# MCU.net
KiCad netlist of a schematic drawn in EAGLE
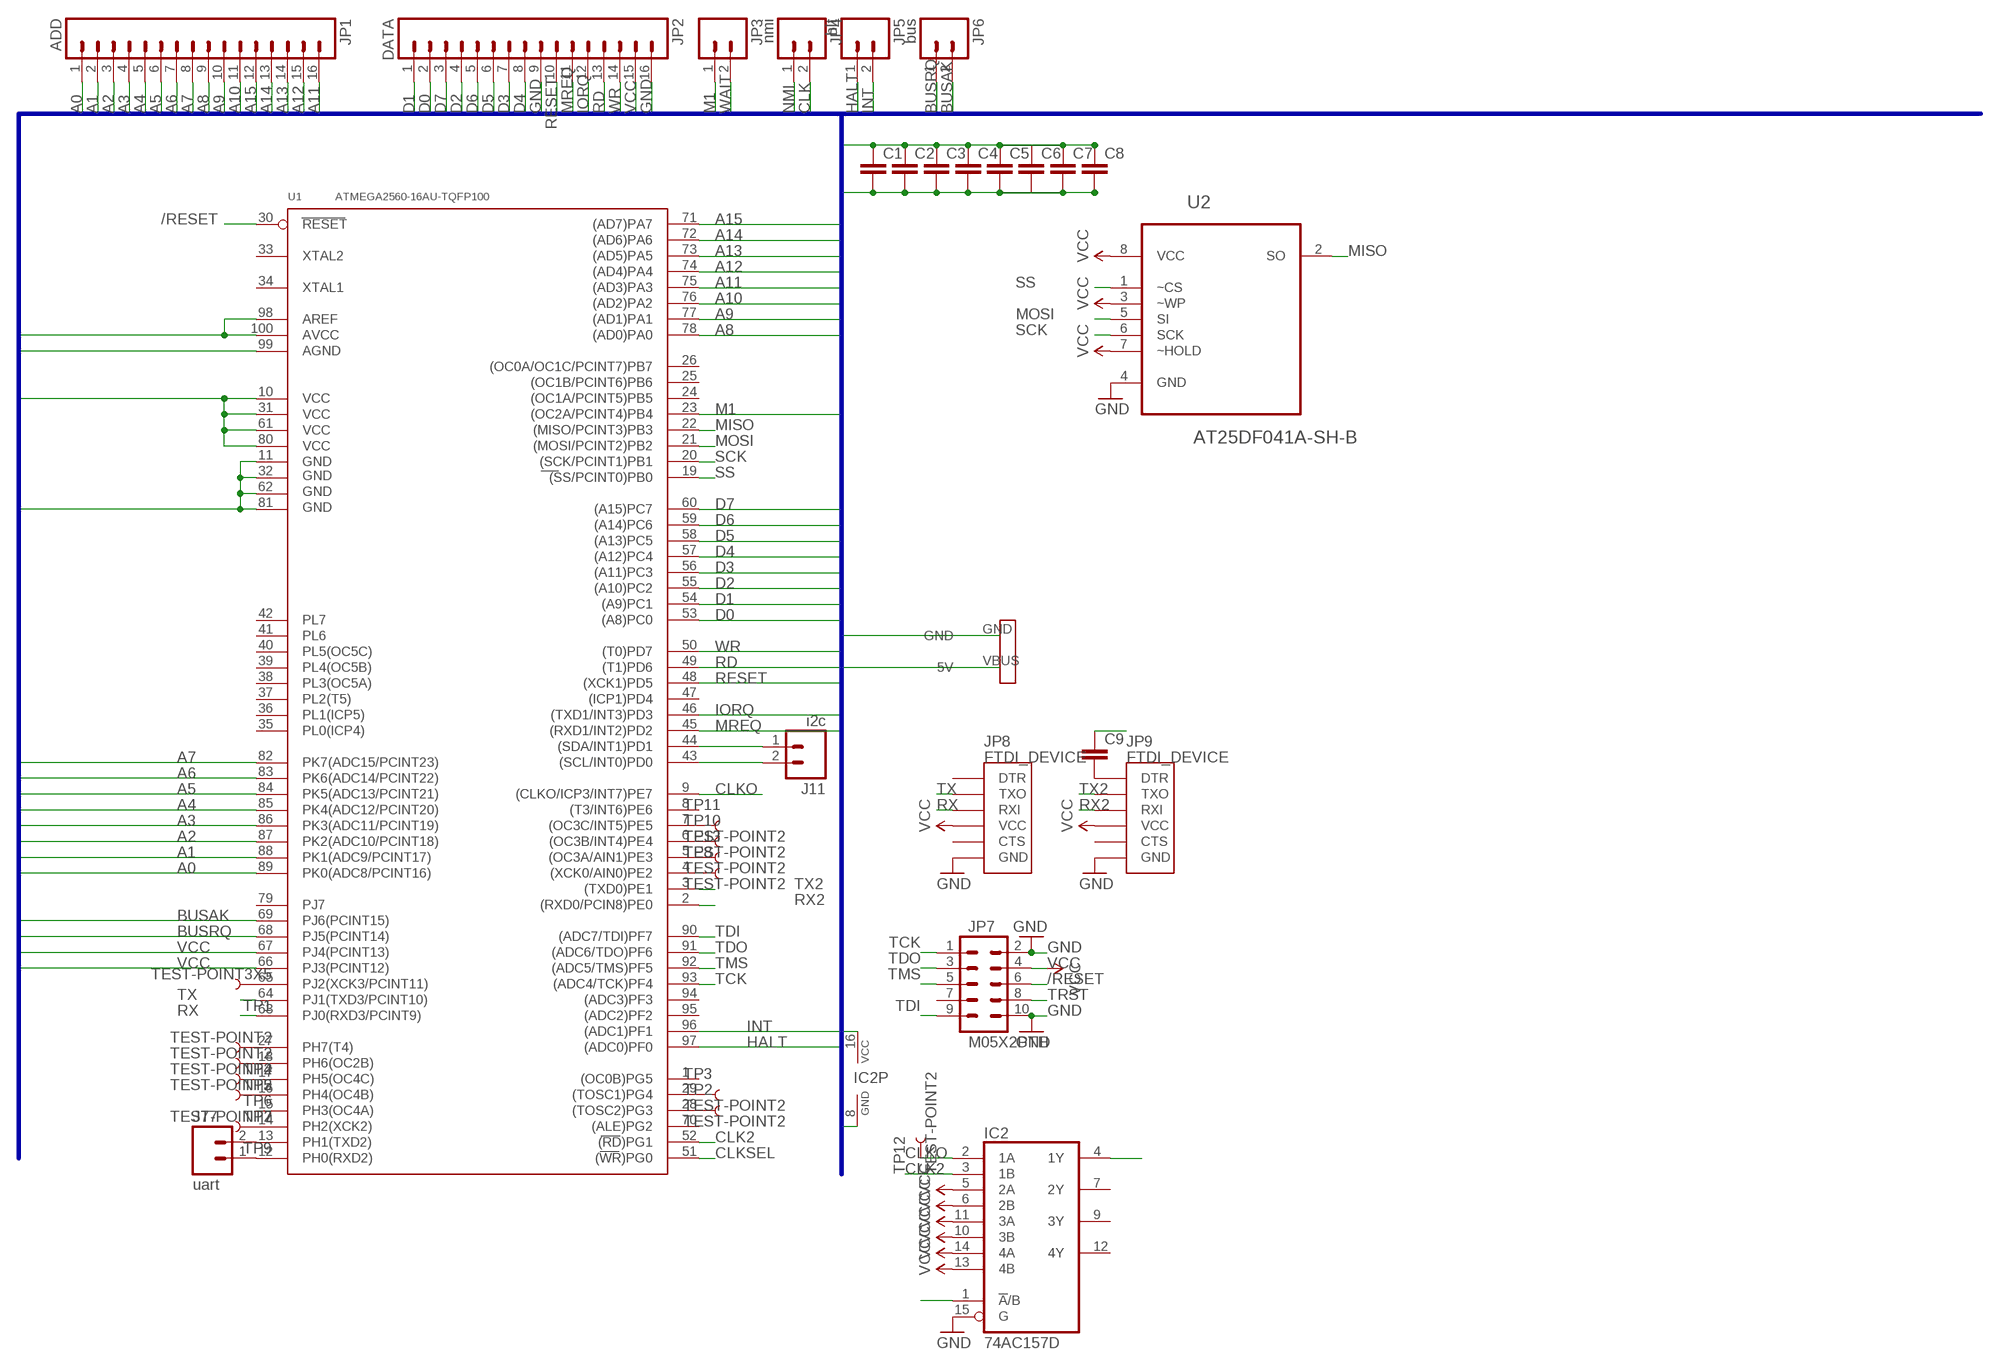
[diagram p0: schematic, sheet 1]

(export (version "E")
  (design (tool "Eeschema 10.0.6"))
  (components
    (comp (ref "C1")
      (value "C-EUC0805")
      (footprint "eagle-import:C0805")
      (libsource (lib "eagle-import") (part "C-EUC0805"))
    )
    (comp (ref "C2")
      (value "C-EUC0805")
      (footprint "eagle-import:C0805")
      (libsource (lib "eagle-import") (part "C-EUC0805"))
    )
    (comp (ref "C3")
      (value "C-EUC0805")
      (footprint "eagle-import:C0805")
      (libsource (lib "eagle-import") (part "C-EUC0805"))
    )
    (comp (ref "C4")
      (value "C-EUC0805")
      (footprint "eagle-import:C0805")
      (libsource (lib "eagle-import") (part "C-EUC0805"))
    )
    (comp (ref "C5")
      (value "C-EUC0805")
      (footprint "eagle-import:C0805")
      (libsource (lib "eagle-import") (part "C-EUC0805"))
    )
    (comp (ref "C6")
      (value "C-EUC0805")
      (footprint "eagle-import:C0805")
      (libsource (lib "eagle-import") (part "C-EUC0805"))
    )
    (comp (ref "C7")
      (value "C-EUC0805")
      (footprint "eagle-import:C0805")
      (libsource (lib "eagle-import") (part "C-EUC0805"))
    )
    (comp (ref "C8")
      (value "C-EUC0805")
      (footprint "eagle-import:C0805")
      (libsource (lib "eagle-import") (part "C-EUC0805"))
    )
    (comp (ref "C9")
      (value "C-EUC0805")
      (footprint "eagle-import:C0805")
      (libsource (lib "eagle-import") (part "C-EUC0805"))
    )
    (comp (ref "IC2")
      (value "74AC157D")
      (footprint "eagle-import:SO16")
      (libsource (lib "eagle-import") (part "74157DAC"))
    )
    (comp (ref "J11")
      (value "i2c")
      (footprint "eagle-import:1X02")
      (libsource (lib "eagle-import") (part "M02PTH"))
    )
    (comp (ref "J77")
      (value "uart")
      (footprint "eagle-import:1X02")
      (libsource (lib "eagle-import") (part "M02PTH"))
    )
    (comp (ref "JP1")
      (value "ADD")
      (footprint "eagle-import:1X16")
      (libsource (lib "eagle-import") (part "M16PTH"))
    )
    (comp (ref "JP2")
      (value "DATA")
      (footprint "eagle-import:1X16")
      (libsource (lib "eagle-import") (part "M16PTH"))
    )
    (comp (ref "JP3")
      (value "M02PTH")
      (footprint "eagle-import:1X02")
      (libsource (lib "eagle-import") (part "M02PTH"))
    )
    (comp (ref "JP4")
      (value "nmi")
      (footprint "eagle-import:1X02")
      (libsource (lib "eagle-import") (part "M02PTH"))
    )
    (comp (ref "JP5")
      (value "hlt")
      (footprint "eagle-import:1X02")
      (libsource (lib "eagle-import") (part "M02PTH"))
    )
    (comp (ref "JP6")
      (value "bus")
      (footprint "eagle-import:1X02")
      (libsource (lib "eagle-import") (part "M02PTH"))
    )
    (comp (ref "JP7")
      (value "M05X2PTH")
      (footprint "eagle-import:AVR_ICSP")
      (libsource (lib "eagle-import") (part "M05X2PTH"))
    )
    (comp (ref "JP8")
      (value "FTDI_DEVICE")
      (footprint "eagle-import:FTDI_DEVICE_SIDE")
      (libsource (lib "eagle-import") (part "FTDI_DEVICE"))
    )
    (comp (ref "JP9")
      (value "FTDI_DEVICE")
      (footprint "eagle-import:FTDI_DEVICE_SIDE")
      (libsource (lib "eagle-import") (part "FTDI_DEVICE"))
    )
    (comp (ref "TP1")
      (value "TEST-POINT3X5")
      (footprint "eagle-import:PAD.03X.05")
      (libsource (lib "eagle-import") (part "TEST-POINT3X5"))
    )
    (comp (ref "TP2")
      (value "TEST-POINT2")
      (footprint "eagle-import:PAD.02X.02")
      (libsource (lib "eagle-import") (part "TEST-POINT2"))
    )
    (comp (ref "TP3")
      (value "TEST-POINT2")
      (footprint "eagle-import:PAD.02X.02")
      (libsource (lib "eagle-import") (part "TEST-POINT2"))
    )
    (comp (ref "TP4")
      (value "TEST-POINT2")
      (footprint "eagle-import:PAD.02X.02")
      (libsource (lib "eagle-import") (part "TEST-POINT2"))
    )
    (comp (ref "TP5")
      (value "TEST-POINT2")
      (footprint "eagle-import:PAD.02X.02")
      (libsource (lib "eagle-import") (part "TEST-POINT2"))
    )
    (comp (ref "TP6")
      (value "TEST-POINT2")
      (footprint "eagle-import:PAD.02X.02")
      (libsource (lib "eagle-import") (part "TEST-POINT2"))
    )
    (comp (ref "TP7")
      (value "TEST-POINT2")
      (footprint "eagle-import:PAD.02X.02")
      (libsource (lib "eagle-import") (part "TEST-POINT2"))
    )
    (comp (ref "TP8")
      (value "TEST-POINT2")
      (footprint "eagle-import:PAD.02X.02")
      (libsource (lib "eagle-import") (part "TEST-POINT2"))
    )
    (comp (ref "TP9")
      (value "TEST-POINT2")
      (footprint "eagle-import:PAD.02X.02")
      (libsource (lib "eagle-import") (part "TEST-POINT2"))
    )
    (comp (ref "TP10")
      (value "TEST-POINT2")
      (footprint "eagle-import:PAD.02X.02")
      (libsource (lib "eagle-import") (part "TEST-POINT2"))
    )
    (comp (ref "TP11")
      (value "TEST-POINT2")
      (footprint "eagle-import:PAD.02X.02")
      (libsource (lib "eagle-import") (part "TEST-POINT2"))
    )
    (comp (ref "TP12")
      (value "TEST-POINT2")
      (footprint "eagle-import:PAD.02X.02")
      (libsource (lib "eagle-import") (part "TEST-POINT2"))
    )
    (comp (ref "TP13")
      (value "TEST-POINT2")
      (footprint "eagle-import:PAD.02X.02")
      (libsource (lib "eagle-import") (part "TEST-POINT2"))
    )
    (comp (ref "U$1")
      (value "USB-MICRO-PWR")
      (footprint "eagle-import:USB-MICROB-PWR")
      (libsource (lib "eagle-import") (part "USB-MICRO-PWR"))
    )
    (comp (ref "U1")
      (value "ATMEGA2560-16AU-TQFP100")
      (footprint "eagle-import:TQFP100-0.5-14X14MM")
      (fields (field (name "MPN") "ATMEGA2560-16AU"))
      (libsource (lib "eagle-import") (part "MCU-ATMEGA2560-16AU(TQFP100)"))
    )
    (comp (ref "U2")
      (value "AT25DF041A-SH-B")
      (footprint "eagle-import:SOIC127P798X216-8N")
      (libsource (lib "eagle-import") (part "AT25DF041A-SH-B"))
    )
  )
  (nets
    (net (code "1") (name "/A0") (class "Default")
      (node (ref "JP1") (pin "1") (pinfunction "1_1") (pintype "passive"))
      (node (ref "U1") (pin "89") (pinfunction "PK0(ADC8/PCINT16)_89") (pintype "bidirectional"))
    )
    (net (code "2") (name "/A1") (class "Default")
      (node (ref "JP1") (pin "2") (pinfunction "2_2") (pintype "passive"))
      (node (ref "U1") (pin "88") (pinfunction "PK1(ADC9/PCINT17)_88") (pintype "bidirectional"))
    )
    (net (code "3") (name "/A2") (class "Default")
      (node (ref "JP1") (pin "3") (pinfunction "3_3") (pintype "passive"))
      (node (ref "U1") (pin "87") (pinfunction "PK2(ADC10/PCINT18)_87") (pintype "bidirectional"))
    )
    (net (code "4") (name "/A3") (class "Default")
      (node (ref "JP1") (pin "4") (pinfunction "4_4") (pintype "passive"))
      (node (ref "U1") (pin "86") (pinfunction "PK3(ADC11/PCINT19)_86") (pintype "bidirectional"))
    )
    (net (code "5") (name "/A4") (class "Default")
      (node (ref "JP1") (pin "5") (pinfunction "5_5") (pintype "passive"))
      (node (ref "U1") (pin "85") (pinfunction "PK4(ADC12/PCINT20)_85") (pintype "bidirectional"))
    )
    (net (code "6") (name "/A5") (class "Default")
      (node (ref "JP1") (pin "6") (pinfunction "6_6") (pintype "passive"))
      (node (ref "U1") (pin "84") (pinfunction "PK5(ADC13/PCINT21)_84") (pintype "bidirectional"))
    )
    (net (code "7") (name "/A6") (class "Default")
      (node (ref "JP1") (pin "7") (pinfunction "7_7") (pintype "passive"))
      (node (ref "U1") (pin "83") (pinfunction "PK6(ADC14/PCINT22)_83") (pintype "bidirectional"))
    )
    (net (code "8") (name "/A7") (class "Default")
      (node (ref "JP1") (pin "8") (pinfunction "8_8") (pintype "passive"))
      (node (ref "U1") (pin "82") (pinfunction "PK7(ADC15/PCINT23)_82") (pintype "bidirectional"))
    )
    (net (code "9") (name "/A8") (class "Default")
      (node (ref "JP1") (pin "9") (pinfunction "9_9") (pintype "passive"))
      (node (ref "U1") (pin "78") (pinfunction "(AD0)PA0_78") (pintype "bidirectional"))
    )
    (net (code "10") (name "/A9") (class "Default")
      (node (ref "JP1") (pin "10") (pinfunction "10_10") (pintype "passive"))
      (node (ref "U1") (pin "77") (pinfunction "(AD1)PA1_77") (pintype "bidirectional"))
    )
    (net (code "11") (name "/A10") (class "Default")
      (node (ref "JP1") (pin "11") (pinfunction "11_11") (pintype "passive"))
      (node (ref "U1") (pin "76") (pinfunction "(AD2)PA2_76") (pintype "bidirectional"))
    )
    (net (code "12") (name "/A11") (class "Default")
      (node (ref "JP1") (pin "16") (pinfunction "16_16") (pintype "passive"))
      (node (ref "U1") (pin "75") (pinfunction "(AD3)PA3_75") (pintype "bidirectional"))
    )
    (net (code "13") (name "/A12") (class "Default")
      (node (ref "JP1") (pin "15") (pinfunction "15_15") (pintype "passive"))
      (node (ref "U1") (pin "74") (pinfunction "(AD4)PA4_74") (pintype "bidirectional"))
    )
    (net (code "14") (name "/A13") (class "Default")
      (node (ref "JP1") (pin "14") (pinfunction "14_14") (pintype "passive"))
      (node (ref "U1") (pin "73") (pinfunction "(AD5)PA5_73") (pintype "bidirectional"))
    )
    (net (code "15") (name "/A14") (class "Default")
      (node (ref "JP1") (pin "13") (pinfunction "13_13") (pintype "passive"))
      (node (ref "U1") (pin "72") (pinfunction "(AD6)PA6_72") (pintype "bidirectional"))
    )
    (net (code "16") (name "/A15") (class "Default")
      (node (ref "JP1") (pin "12") (pinfunction "12_12") (pintype "passive"))
      (node (ref "U1") (pin "71") (pinfunction "(AD7)PA7_71") (pintype "bidirectional"))
    )
    (net (code "17") (name "/BUSAK") (class "Default")
      (node (ref "JP6") (pin "2") (pinfunction "2_2") (pintype "passive"))
      (node (ref "U1") (pin "69") (pinfunction "PJ6(PCINT15)_69") (pintype "bidirectional"))
    )
    (net (code "18") (name "/BUSRQ") (class "Default")
      (node (ref "JP6") (pin "1") (pinfunction "1_1") (pintype "passive"))
      (node (ref "U1") (pin "68") (pinfunction "PJ5(PCINT14)_68") (pintype "bidirectional"))
    )
    (net (code "19") (name "/CLK") (class "Default")
      (node (ref "IC2") (pin "4") (pinfunction "1Y_4") (pintype "output"))
      (node (ref "JP4") (pin "2") (pinfunction "2_2") (pintype "passive"))
    )
    (net (code "20") (name "/CLK2") (class "Default")
      (node (ref "IC2") (pin "3") (pinfunction "1B_3") (pintype "input"))
      (node (ref "U1") (pin "52") (pinfunction "(RD)PG1_52") (pintype "bidirectional"))
    )
    (net (code "21") (name "/CLKO") (class "Default")
      (node (ref "IC2") (pin "2") (pinfunction "1A_2") (pintype "input"))
      (node (ref "TP12") (pin "P$1") (pinfunction "1_P$1") (pintype "bidirectional"))
      (node (ref "U1") (pin "9") (pinfunction "(CLKO/ICP3/INT7)PE7_9") (pintype "bidirectional"))
    )
    (net (code "22") (name "/CLKSEL") (class "Default")
      (node (ref "IC2") (pin "1") (pinfunction "~{A}/B_1") (pintype "input"))
      (node (ref "U1") (pin "51") (pinfunction "(WR)PG0_51") (pintype "bidirectional"))
    )
    (net (code "23") (name "/D0") (class "Default")
      (node (ref "JP2") (pin "2") (pinfunction "2_2") (pintype "passive"))
      (node (ref "U1") (pin "53") (pinfunction "(A8)PC0_53") (pintype "bidirectional"))
    )
    (net (code "24") (name "/D1") (class "Default")
      (node (ref "JP2") (pin "1") (pinfunction "1_1") (pintype "passive"))
      (node (ref "U1") (pin "54") (pinfunction "(A9)PC1_54") (pintype "bidirectional"))
    )
    (net (code "25") (name "/D2") (class "Default")
      (node (ref "JP2") (pin "4") (pinfunction "4_4") (pintype "passive"))
      (node (ref "U1") (pin "55") (pinfunction "(A10)PC2_55") (pintype "bidirectional"))
    )
    (net (code "26") (name "/D3") (class "Default")
      (node (ref "JP2") (pin "7") (pinfunction "7_7") (pintype "passive"))
      (node (ref "U1") (pin "56") (pinfunction "(A11)PC3_56") (pintype "bidirectional"))
    )
    (net (code "27") (name "/D4") (class "Default")
      (node (ref "JP2") (pin "8") (pinfunction "8_8") (pintype "passive"))
      (node (ref "U1") (pin "57") (pinfunction "(A12)PC4_57") (pintype "bidirectional"))
    )
    (net (code "28") (name "/D5") (class "Default")
      (node (ref "JP2") (pin "6") (pinfunction "6_6") (pintype "passive"))
      (node (ref "U1") (pin "58") (pinfunction "(A13)PC5_58") (pintype "bidirectional"))
    )
    (net (code "29") (name "/D6") (class "Default")
      (node (ref "JP2") (pin "5") (pinfunction "5_5") (pintype "passive"))
      (node (ref "U1") (pin "59") (pinfunction "(A14)PC6_59") (pintype "bidirectional"))
    )
    (net (code "30") (name "/D7") (class "Default")
      (node (ref "JP2") (pin "3") (pinfunction "3_3") (pintype "passive"))
      (node (ref "U1") (pin "60") (pinfunction "(A15)PC7_60") (pintype "bidirectional"))
    )
    (net (code "31") (name "/HALT") (class "Default")
      (node (ref "JP5") (pin "1") (pinfunction "1_1") (pintype "passive"))
      (node (ref "U1") (pin "97") (pinfunction "(ADC0)PF0_97") (pintype "bidirectional"))
    )
    (net (code "32") (name "/INT") (class "Default")
      (node (ref "JP5") (pin "2") (pinfunction "2_2") (pintype "passive"))
      (node (ref "U1") (pin "96") (pinfunction "(ADC1)PF1_96") (pintype "bidirectional"))
    )
    (net (code "33") (name "/IORQ") (class "Default")
      (node (ref "JP2") (pin "12") (pinfunction "12_12") (pintype "passive"))
      (node (ref "U1") (pin "46") (pinfunction "(TXD1/INT3)PD3_46") (pintype "bidirectional"))
    )
    (net (code "34") (name "/M1") (class "Default")
      (node (ref "JP3") (pin "1") (pinfunction "1_1") (pintype "passive"))
      (node (ref "U1") (pin "23") (pinfunction "(OC2A/PCINT4)PB4_23") (pintype "bidirectional"))
    )
    (net (code "35") (name "/MISO") (class "Default")
      (node (ref "U1") (pin "22") (pinfunction "(MISO/PCINT3)PB3_22") (pintype "bidirectional"))
      (node (ref "U2") (pin "2") (pinfunction "SO_2") (pintype "output"))
    )
    (net (code "36") (name "/MOSI") (class "Default")
      (node (ref "U1") (pin "21") (pinfunction "(MOSI/PCINT2)PB2_21") (pintype "bidirectional"))
      (node (ref "U2") (pin "5") (pinfunction "SI_5") (pintype "input"))
    )
    (net (code "37") (name "/MREQ") (class "Default")
      (node (ref "JP2") (pin "11") (pinfunction "11_11") (pintype "passive"))
      (node (ref "U1") (pin "45") (pinfunction "(RXD1/INT2)PD2_45") (pintype "bidirectional"))
    )
    (net (code "38") (name "/NMI") (class "Default")
      (node (ref "JP4") (pin "1") (pinfunction "1_1") (pintype "passive"))
    )
    (net (code "39") (name "/RD") (class "Default")
      (node (ref "JP2") (pin "13") (pinfunction "13_13") (pintype "passive"))
      (node (ref "U1") (pin "49") (pinfunction "(T1)PD6_49") (pintype "bidirectional"))
    )
    (net (code "40") (name "/RESET") (class "Default")
      (node (ref "JP2") (pin "10") (pinfunction "10_10") (pintype "passive"))
      (node (ref "U1") (pin "48") (pinfunction "(XCK1)PD5_48") (pintype "bidirectional"))
    )
    (net (code "41") (name "/RX") (class "Default")
      (node (ref "JP8") (pin "P$3") (pinfunction "RXI_P$3") (pintype "bidirectional"))
      (node (ref "U1") (pin "63") (pinfunction "PJ0(RXD3/PCINT9)_63") (pintype "bidirectional"))
    )
    (net (code "42") (name "/RX2") (class "Default")
      (node (ref "JP9") (pin "P$3") (pinfunction "RXI_P$3") (pintype "bidirectional"))
      (node (ref "U1") (pin "2") (pinfunction "(RXD0/PCIN8)PE0_2") (pintype "bidirectional"))
    )
    (net (code "43") (name "/SCK") (class "Default")
      (node (ref "U1") (pin "20") (pinfunction "(SCK/PCINT1)PB1_20") (pintype "bidirectional"))
      (node (ref "U2") (pin "6") (pinfunction "SCK_6") (pintype "input"))
    )
    (net (code "44") (name "/SS") (class "Default")
      (node (ref "U1") (pin "19") (pinfunction "(SS/PCINT0)PB0_19") (pintype "bidirectional"))
      (node (ref "U2") (pin "1") (pinfunction "~{CS}_1") (pintype "input"))
    )
    (net (code "45") (name "/TCK") (class "Default")
      (node (ref "JP7") (pin "1") (pinfunction "1_1") (pintype "passive"))
      (node (ref "U1") (pin "93") (pinfunction "(ADC4/TCK)PF4_93") (pintype "bidirectional"))
    )
    (net (code "46") (name "/TDI") (class "Default")
      (node (ref "JP7") (pin "9") (pinfunction "9_9") (pintype "passive"))
      (node (ref "U1") (pin "90") (pinfunction "(ADC7/TDI)PF7_90") (pintype "bidirectional"))
    )
    (net (code "47") (name "/TDO") (class "Default")
      (node (ref "JP7") (pin "3") (pinfunction "3_3") (pintype "passive"))
      (node (ref "U1") (pin "91") (pinfunction "(ADC6/TDO)PF6_91") (pintype "bidirectional"))
    )
    (net (code "48") (name "/TMS") (class "Default")
      (node (ref "JP7") (pin "5") (pinfunction "5_5") (pintype "passive"))
      (node (ref "U1") (pin "92") (pinfunction "(ADC5/TMS)PF5_92") (pintype "bidirectional"))
    )
    (net (code "49") (name "/TRST") (class "Default")
      (node (ref "JP7") (pin "8") (pinfunction "8_8") (pintype "passive"))
    )
    (net (code "50") (name "/TX") (class "Default")
      (node (ref "JP8") (pin "P$2") (pinfunction "TXO_P$2") (pintype "bidirectional"))
      (node (ref "U1") (pin "64") (pinfunction "PJ1(TXD3/PCINT10)_64") (pintype "bidirectional"))
    )
    (net (code "51") (name "/TX2") (class "Default")
      (node (ref "JP9") (pin "P$2") (pinfunction "TXO_P$2") (pintype "bidirectional"))
      (node (ref "U1") (pin "3") (pinfunction "(TXD0)PE1_3") (pintype "bidirectional"))
    )
    (net (code "52") (name "/WAIT") (class "Default")
      (node (ref "JP3") (pin "2") (pinfunction "2_2") (pintype "passive"))
    )
    (net (code "53") (name "/WR") (class "Default")
      (node (ref "JP2") (pin "14") (pinfunction "14_14") (pintype "passive"))
      (node (ref "U1") (pin "50") (pinfunction "(T0)PD7_50") (pintype "bidirectional"))
    )
    (net (code "54") (name "/{slash}RESET") (class "Default")
      (node (ref "C9") (pin "1") (pinfunction "1_1") (pintype "passive"))
      (node (ref "JP7") (pin "6") (pinfunction "6_6") (pintype "passive"))
      (node (ref "U1") (pin "30") (pinfunction "RESET_30") (pintype "input"))
    )
    (net (code "55") (name "GND") (class "Default")
      (node (ref "C1") (pin "2") (pinfunction "2_2") (pintype "passive"))
      (node (ref "C2") (pin "2") (pinfunction "2_2") (pintype "passive"))
      (node (ref "C3") (pin "2") (pinfunction "2_2") (pintype "passive"))
      (node (ref "C4") (pin "2") (pinfunction "2_2") (pintype "passive"))
      (node (ref "C5") (pin "2") (pinfunction "2_2") (pintype "passive"))
      (node (ref "C6") (pin "2") (pinfunction "2_2") (pintype "passive"))
      (node (ref "C7") (pin "2") (pinfunction "2_2") (pintype "passive"))
      (node (ref "C8") (pin "2") (pinfunction "2_2") (pintype "passive"))
      (node (ref "IC2") (pin "15") (pinfunction "G_15") (pintype "input"))
      (node (ref "IC2") (pin "8") (pinfunction "GND_8") (pintype "power_in"))
      (node (ref "JP2") (pin "16") (pinfunction "16_16") (pintype "passive"))
      (node (ref "JP2") (pin "9") (pinfunction "9_9") (pintype "passive"))
      (node (ref "JP7") (pin "10") (pinfunction "10_10") (pintype "passive"))
      (node (ref "JP7") (pin "2") (pinfunction "2_2") (pintype "passive"))
      (node (ref "JP8") (pin "P$6") (pinfunction "GND_P$6") (pintype "bidirectional"))
      (node (ref "JP9") (pin "P$6") (pinfunction "GND_P$6") (pintype "bidirectional"))
      (node (ref "U$1") (pin "GND") (pinfunction "GND_GND") (pintype "bidirectional"))
      (node (ref "U1") (pin "11") (pinfunction "GND_11") (pintype "power_in"))
      (node (ref "U1") (pin "32") (pinfunction "GND1_32") (pintype "power_in"))
      (node (ref "U1") (pin "62") (pinfunction "GND2_62") (pintype "power_in"))
      (node (ref "U1") (pin "81") (pinfunction "GND3_81") (pintype "power_in"))
      (node (ref "U1") (pin "99") (pinfunction "AGND_99") (pintype "power_in"))
      (node (ref "U2") (pin "4") (pinfunction "GND_4") (pintype "passive"))
    )
    (net (code "56") (name "Net-(JP9-DTR)") (class "Default")
      (node (ref "C9") (pin "2") (pinfunction "2_2") (pintype "passive"))
      (node (ref "JP9") (pin "P$1") (pinfunction "DTR_P$1") (pintype "bidirectional"))
    )
    (net (code "57") (name "Net-(TP1-1)") (class "Default")
      (node (ref "TP1") (pin "P$1") (pinfunction "1_P$1") (pintype "bidirectional"))
      (node (ref "U1") (pin "65") (pinfunction "PJ2(XCK3/PCINT11)_65") (pintype "bidirectional"))
    )
    (net (code "58") (name "Net-(TP2-1)") (class "Default")
      (node (ref "TP2") (pin "P$1") (pinfunction "1_P$1") (pintype "bidirectional"))
      (node (ref "U1") (pin "28") (pinfunction "(TOSC2)PG3_28") (pintype "bidirectional"))
    )
    (net (code "59") (name "Net-(TP3-1)") (class "Default")
      (node (ref "TP3") (pin "P$1") (pinfunction "1_P$1") (pintype "bidirectional"))
      (node (ref "U1") (pin "29") (pinfunction "(TOSC1)PG4_29") (pintype "bidirectional"))
    )
    (net (code "60") (name "Net-(TP4-1)") (class "Default")
      (node (ref "TP4") (pin "P$1") (pinfunction "1_P$1") (pintype "bidirectional"))
      (node (ref "U1") (pin "27") (pinfunction "PH7(T4)_27") (pintype "bidirectional"))
    )
    (net (code "61") (name "Net-(TP5-1)") (class "Default")
      (node (ref "TP5") (pin "P$1") (pinfunction "1_P$1") (pintype "bidirectional"))
      (node (ref "U1") (pin "18") (pinfunction "PH6(OC2B)_18") (pintype "bidirectional"))
    )
    (net (code "62") (name "Net-(TP6-1)") (class "Default")
      (node (ref "TP6") (pin "P$1") (pinfunction "1_P$1") (pintype "bidirectional"))
      (node (ref "U1") (pin "17") (pinfunction "PH5(OC4C)_17") (pintype "bidirectional"))
    )
    (net (code "63") (name "Net-(TP7-1)") (class "Default")
      (node (ref "TP7") (pin "P$1") (pinfunction "1_P$1") (pintype "bidirectional"))
      (node (ref "U1") (pin "16") (pinfunction "PH4(OC4B)_16") (pintype "bidirectional"))
    )
    (net (code "64") (name "Net-(TP8-1)") (class "Default")
      (node (ref "TP8") (pin "P$1") (pinfunction "1_P$1") (pintype "bidirectional"))
      (node (ref "U1") (pin "4") (pinfunction "(XCK0/AIN0)PE2_4") (pintype "bidirectional"))
    )
    (net (code "65") (name "Net-(TP9-1)") (class "Default")
      (node (ref "TP9") (pin "P$1") (pinfunction "1_P$1") (pintype "bidirectional"))
      (node (ref "U1") (pin "14") (pinfunction "PH2(XCK2)_14") (pintype "bidirectional"))
    )
    (net (code "66") (name "Net-(TP10-1)") (class "Default")
      (node (ref "TP10") (pin "P$1") (pinfunction "1_P$1") (pintype "bidirectional"))
      (node (ref "U1") (pin "6") (pinfunction "(OC3B/INT4)PE4_6") (pintype "bidirectional"))
    )
    (net (code "67") (name "Net-(TP11-1)") (class "Default")
      (node (ref "TP11") (pin "P$1") (pinfunction "1_P$1") (pintype "bidirectional"))
      (node (ref "U1") (pin "7") (pinfunction "(OC3C/INT5)PE5_7") (pintype "bidirectional"))
    )
    (net (code "68") (name "Net-(TP13-1)") (class "Default")
      (node (ref "TP13") (pin "P$1") (pinfunction "1_P$1") (pintype "bidirectional"))
      (node (ref "U1") (pin "5") (pinfunction "(OC3A/AIN1)PE3_5") (pintype "bidirectional"))
    )
    (net (code "69") (name "Net-(U1-(SCL{slash}INT0)PD0)") (class "Default")
      (node (ref "J11") (pin "2") (pinfunction "2_2") (pintype "passive"))
      (node (ref "U1") (pin "43") (pinfunction "(SCL/INT0)PD0_43") (pintype "bidirectional"))
    )
    (net (code "70") (name "Net-(U1-(SDA{slash}INT1)PD1)") (class "Default")
      (node (ref "J11") (pin "1") (pinfunction "1_1") (pintype "passive"))
      (node (ref "U1") (pin "44") (pinfunction "(SDA/INT1)PD1_44") (pintype "bidirectional"))
    )
    (net (code "71") (name "Net-(U1-PH0(RXD2))") (class "Default")
      (node (ref "J77") (pin "1") (pinfunction "1_1") (pintype "passive"))
      (node (ref "U1") (pin "12") (pinfunction "PH0(RXD2)_12") (pintype "bidirectional"))
    )
    (net (code "72") (name "Net-(U1-PH1(TXD2))") (class "Default")
      (node (ref "J77") (pin "2") (pinfunction "2_2") (pintype "passive"))
      (node (ref "U1") (pin "13") (pinfunction "PH1(TXD2)_13") (pintype "bidirectional"))
    )
    (net (code "73") (name "VCC") (class "Default")
      (node (ref "C1") (pin "1") (pinfunction "1_1") (pintype "passive"))
      (node (ref "C2") (pin "1") (pinfunction "1_1") (pintype "passive"))
      (node (ref "C3") (pin "1") (pinfunction "1_1") (pintype "passive"))
      (node (ref "C4") (pin "1") (pinfunction "1_1") (pintype "passive"))
      (node (ref "C5") (pin "1") (pinfunction "1_1") (pintype "passive"))
      (node (ref "C6") (pin "1") (pinfunction "1_1") (pintype "passive"))
      (node (ref "C7") (pin "1") (pinfunction "1_1") (pintype "passive"))
      (node (ref "C8") (pin "1") (pinfunction "1_1") (pintype "passive"))
      (node (ref "IC2") (pin "10") (pinfunction "3B_10") (pintype "input"))
      (node (ref "IC2") (pin "11") (pinfunction "3A_11") (pintype "input"))
      (node (ref "IC2") (pin "13") (pinfunction "4B_13") (pintype "input"))
      (node (ref "IC2") (pin "14") (pinfunction "4A_14") (pintype "input"))
      (node (ref "IC2") (pin "16") (pinfunction "VCC_16") (pintype "power_in"))
      (node (ref "IC2") (pin "5") (pinfunction "2A_5") (pintype "input"))
      (node (ref "IC2") (pin "6") (pinfunction "2B_6") (pintype "input"))
      (node (ref "JP2") (pin "15") (pinfunction "15_15") (pintype "passive"))
      (node (ref "JP7") (pin "4") (pinfunction "4_4") (pintype "passive"))
      (node (ref "JP8") (pin "P$4") (pinfunction "VCC_P$4") (pintype "bidirectional"))
      (node (ref "JP9") (pin "P$4") (pinfunction "VCC_P$4") (pintype "bidirectional"))
      (node (ref "U$1") (pin "VBUS") (pinfunction "5V_VBUS") (pintype "bidirectional"))
      (node (ref "U1") (pin "10") (pinfunction "VCC_10") (pintype "power_in"))
      (node (ref "U1") (pin "100") (pinfunction "AVCC_100") (pintype "power_in"))
      (node (ref "U1") (pin "31") (pinfunction "VCC1_31") (pintype "power_in"))
      (node (ref "U1") (pin "61") (pinfunction "VCC2_61") (pintype "power_in"))
      (node (ref "U1") (pin "66") (pinfunction "PJ3(PCINT12)_66") (pintype "bidirectional"))
      (node (ref "U1") (pin "67") (pinfunction "PJ4(PCINT13)_67") (pintype "bidirectional"))
      (node (ref "U1") (pin "80") (pinfunction "VCC3_80") (pintype "power_in"))
      (node (ref "U1") (pin "98") (pinfunction "AREF_98") (pintype "bidirectional"))
      (node (ref "U2") (pin "3") (pinfunction "~{WP}_3") (pintype "input"))
      (node (ref "U2") (pin "7") (pinfunction "~{HOLD}_7") (pintype "input"))
      (node (ref "U2") (pin "8") (pinfunction "VCC_8") (pintype "power_in"))
    )
    (net (code "74") (name "unconnected-(IC2A-2Y-Pad7)") (class "Default")
      (node (ref "IC2") (pin "7") (pinfunction "2Y_7") (pintype "output"))
    )
    (net (code "75") (name "unconnected-(IC2A-3Y-Pad9)") (class "Default")
      (node (ref "IC2") (pin "9") (pinfunction "3Y_9") (pintype "output"))
    )
    (net (code "76") (name "unconnected-(IC2A-4Y-Pad12)") (class "Default")
      (node (ref "IC2") (pin "12") (pinfunction "4Y_12") (pintype "output"))
    )
    (net (code "77") (name "unconnected-(JP7-Pad7)") (class "Default")
      (node (ref "JP7") (pin "7") (pinfunction "7_7") (pintype "passive"))
    )
    (net (code "78") (name "unconnected-(JP8-CTS-PadP$5)") (class "Default")
      (node (ref "JP8") (pin "P$5") (pinfunction "CTS_P$5") (pintype "bidirectional"))
    )
    (net (code "79") (name "unconnected-(JP8-DTR-PadP$1)") (class "Default")
      (node (ref "JP8") (pin "P$1") (pinfunction "DTR_P$1") (pintype "bidirectional"))
    )
    (net (code "80") (name "unconnected-(JP9-CTS-PadP$5)") (class "Default")
      (node (ref "JP9") (pin "P$5") (pinfunction "CTS_P$5") (pintype "bidirectional"))
    )
    (net (code "81") (name "unconnected-(U1-(ADC2)PF2-Pad95)") (class "Default")
      (node (ref "U1") (pin "95") (pinfunction "(ADC2)PF2_95") (pintype "bidirectional"))
    )
    (net (code "82") (name "unconnected-(U1-(ADC3)PF3-Pad94)") (class "Default")
      (node (ref "U1") (pin "94") (pinfunction "(ADC3)PF3_94") (pintype "bidirectional"))
    )
    (net (code "83") (name "unconnected-(U1-(ALE)PG2-Pad70)") (class "Default")
      (node (ref "U1") (pin "70") (pinfunction "(ALE)PG2_70") (pintype "bidirectional"))
    )
    (net (code "84") (name "unconnected-(U1-(ICP1)PD4-Pad47)") (class "Default")
      (node (ref "U1") (pin "47") (pinfunction "(ICP1)PD4_47") (pintype "bidirectional"))
    )
    (net (code "85") (name "unconnected-(U1-(OC0A{slash}OC1C{slash}PCINT7)PB7-Pad26)") (class "Default")
      (node (ref "U1") (pin "26") (pinfunction "(OC0A/OC1C/PCINT7)PB7_26") (pintype "bidirectional"))
    )
    (net (code "86") (name "unconnected-(U1-(OC0B)PG5-Pad1)") (class "Default")
      (node (ref "U1") (pin "1") (pinfunction "(OC0B)PG5_1") (pintype "bidirectional"))
    )
    (net (code "87") (name "unconnected-(U1-(OC1A{slash}PCINT5)PB5-Pad24)") (class "Default")
      (node (ref "U1") (pin "24") (pinfunction "(OC1A/PCINT5)PB5_24") (pintype "bidirectional"))
    )
    (net (code "88") (name "unconnected-(U1-(OC1B{slash}PCINT6)PB6-Pad25)") (class "Default")
      (node (ref "U1") (pin "25") (pinfunction "(OC1B/PCINT6)PB6_25") (pintype "bidirectional"))
    )
    (net (code "89") (name "unconnected-(U1-(T3{slash}INT6)PE6-Pad8)") (class "Default")
      (node (ref "U1") (pin "8") (pinfunction "(T3/INT6)PE6_8") (pintype "bidirectional"))
    )
    (net (code "90") (name "unconnected-(U1-PH3(OC4A)-Pad15)") (class "Default")
      (node (ref "U1") (pin "15") (pinfunction "PH3(OC4A)_15") (pintype "bidirectional"))
    )
    (net (code "91") (name "unconnected-(U1-PJ7-Pad79)") (class "Default")
      (node (ref "U1") (pin "79") (pinfunction "PJ7_79") (pintype "bidirectional"))
    )
    (net (code "92") (name "unconnected-(U1-PL0(ICP4)-Pad35)") (class "Default")
      (node (ref "U1") (pin "35") (pinfunction "PL0(ICP4)_35") (pintype "bidirectional"))
    )
    (net (code "93") (name "unconnected-(U1-PL1(ICP5)-Pad36)") (class "Default")
      (node (ref "U1") (pin "36") (pinfunction "PL1(ICP5)_36") (pintype "bidirectional"))
    )
    (net (code "94") (name "unconnected-(U1-PL2(T5)-Pad37)") (class "Default")
      (node (ref "U1") (pin "37") (pinfunction "PL2(T5)_37") (pintype "bidirectional"))
    )
    (net (code "95") (name "unconnected-(U1-PL3(OC5A)-Pad38)") (class "Default")
      (node (ref "U1") (pin "38") (pinfunction "PL3(OC5A)_38") (pintype "bidirectional"))
    )
    (net (code "96") (name "unconnected-(U1-PL4(OC5B)-Pad39)") (class "Default")
      (node (ref "U1") (pin "39") (pinfunction "PL4(OC5B)_39") (pintype "bidirectional"))
    )
    (net (code "97") (name "unconnected-(U1-PL5(OC5C)-Pad40)") (class "Default")
      (node (ref "U1") (pin "40") (pinfunction "PL5(OC5C)_40") (pintype "bidirectional"))
    )
    (net (code "98") (name "unconnected-(U1-PL6-Pad41)") (class "Default")
      (node (ref "U1") (pin "41") (pinfunction "PL6_41") (pintype "bidirectional"))
    )
    (net (code "99") (name "unconnected-(U1-PL7-Pad42)") (class "Default")
      (node (ref "U1") (pin "42") (pinfunction "PL7_42") (pintype "bidirectional"))
    )
    (net (code "100") (name "unconnected-(U1-XTAL1-Pad34)") (class "Default")
      (node (ref "U1") (pin "34") (pinfunction "XTAL1_34") (pintype "input"))
    )
    (net (code "101") (name "unconnected-(U1-XTAL2-Pad33)") (class "Default")
      (node (ref "U1") (pin "33") (pinfunction "XTAL2_33") (pintype "output"))
    )
  )
)
